# MCU.net
KiCad netlist of a schematic drawn in Altium Designer
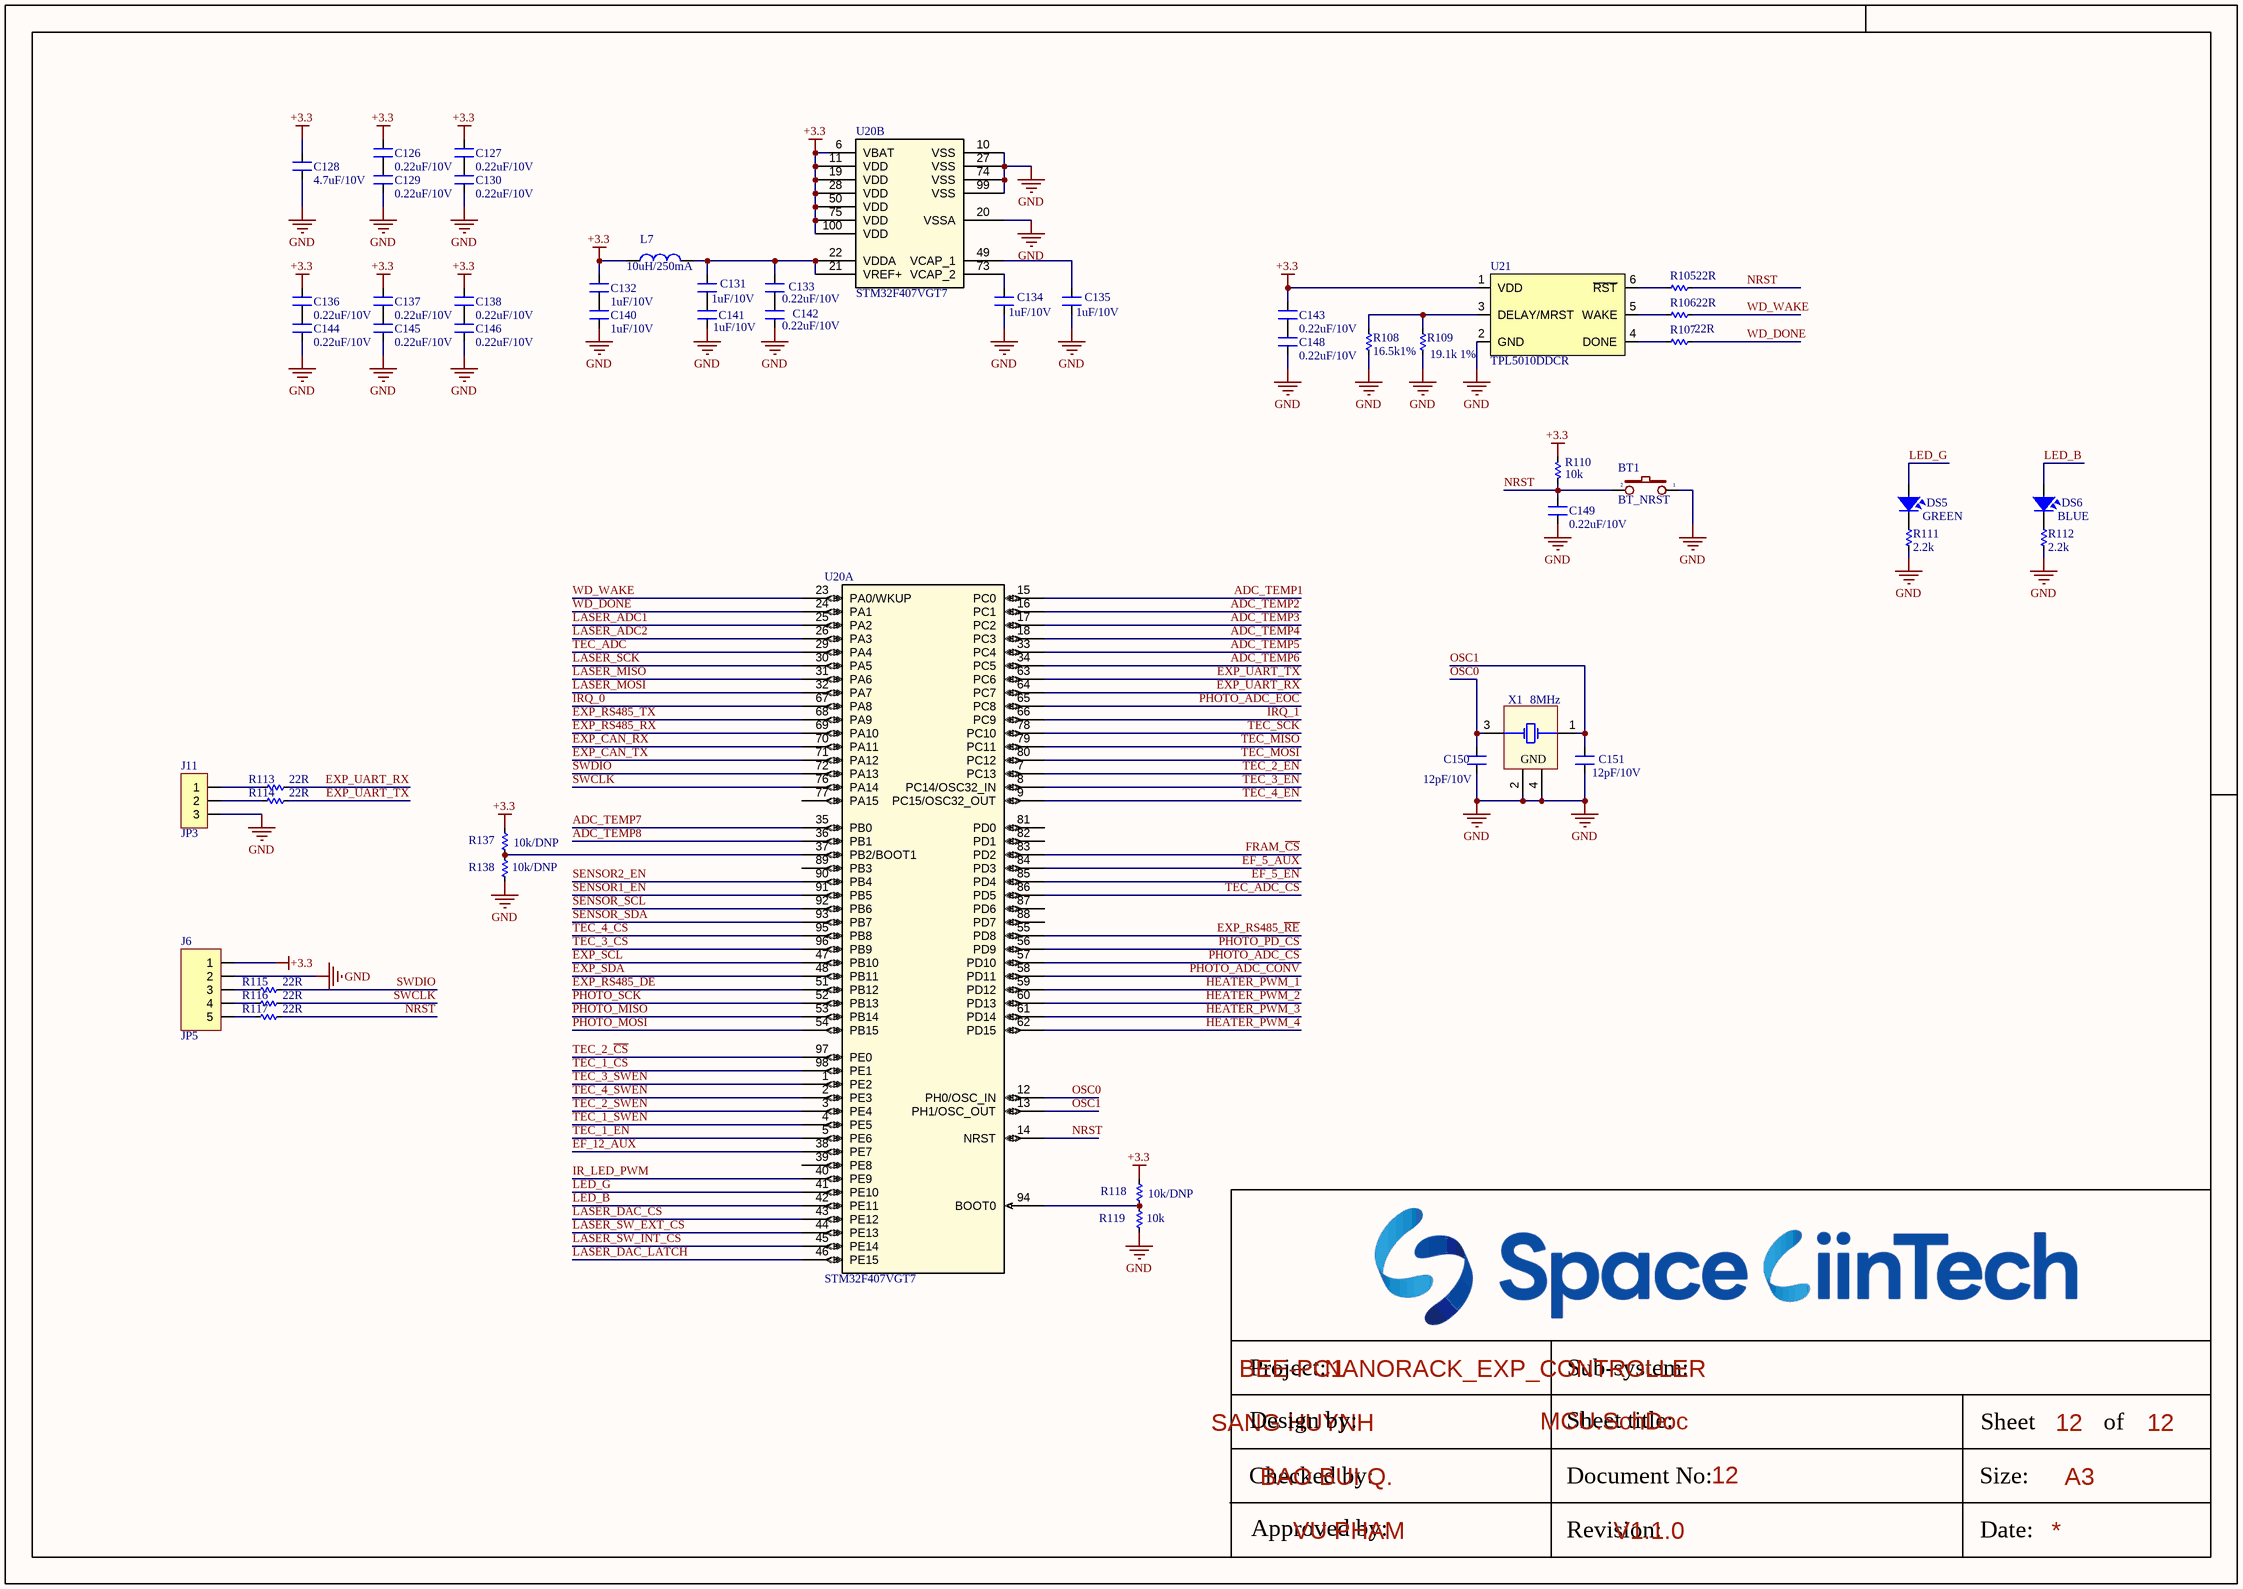
[diagram p0: MCU.SchDoc]

(export (version "E")
  (design (tool "Eeschema 10.0.6"))
  (components
    (comp (ref "BT1")
      (value "BT_NRST")
      (footprint "SW1-SMD")
      (description "Switch button 2 pin")
      (libsource (lib "Sang_library") (part "SW2"))
    )
    (comp (ref "C126")
      (value "0.22uF/10V")
      (footprint "CAP_C_1608X80")
      (libsource (lib "Sang_library") (part "Capacitors"))
    )
    (comp (ref "C127")
      (value "0.22uF/10V")
      (footprint "CAP_C_1608X80")
      (libsource (lib "Sang_library") (part "Capacitors"))
    )
    (comp (ref "C128")
      (value "4.7uF/10V")
      (footprint "CAP_C_1608X80")
      (libsource (lib "Sang_library") (part "Capacitors"))
    )
    (comp (ref "C129")
      (value "0.22uF/10V")
      (footprint "CAP_C_1608X80")
      (libsource (lib "Sang_library") (part "Capacitors"))
    )
    (comp (ref "C130")
      (value "0.22uF/10V")
      (footprint "CAP_C_1608X80")
      (libsource (lib "Sang_library") (part "Capacitors"))
    )
    (comp (ref "C131")
      (value "1uF/10V")
      (footprint "CAP_C_1608X80")
      (libsource (lib "Sang_library") (part "Capacitors"))
    )
    (comp (ref "C132")
      (value "1uF/10V")
      (footprint "CAP_C_1608X80")
      (libsource (lib "Sang_library") (part "Capacitors"))
    )
    (comp (ref "C133")
      (value "0.22uF/10V")
      (footprint "CAP_C_1608X80")
      (libsource (lib "Sang_library") (part "Capacitors"))
    )
    (comp (ref "C134")
      (value "1uF/10V")
      (footprint "CAP_C_1608X80")
      (libsource (lib "Sang_library") (part "Capacitors"))
    )
    (comp (ref "C135")
      (value "1uF/10V")
      (footprint "CAP_C_1608X80")
      (libsource (lib "Sang_library") (part "Capacitors"))
    )
    (comp (ref "C136")
      (value "0.22uF/10V")
      (footprint "CAP_C_1608X80")
      (libsource (lib "Sang_library") (part "Capacitors"))
    )
    (comp (ref "C137")
      (value "0.22uF/10V")
      (footprint "CAP_C_1608X80")
      (libsource (lib "Sang_library") (part "Capacitors"))
    )
    (comp (ref "C138")
      (value "0.22uF/10V")
      (footprint "CAP_C_1608X80")
      (libsource (lib "Sang_library") (part "Capacitors"))
    )
    (comp (ref "C140")
      (value "1uF/10V")
      (footprint "CAP_C_1608X80")
      (libsource (lib "Sang_library") (part "Capacitors"))
    )
    (comp (ref "C141")
      (value "1uF/10V")
      (footprint "CAP_C_1608X80")
      (libsource (lib "Sang_library") (part "Capacitors"))
    )
    (comp (ref "C142")
      (value "0.22uF/10V")
      (footprint "CAP_C_1608X80")
      (libsource (lib "Sang_library") (part "Capacitors"))
    )
    (comp (ref "C143")
      (value "0.22uF/10V")
      (footprint "CAP_C_1608X80")
      (libsource (lib "Sang_library") (part "Capacitors"))
    )
    (comp (ref "C144")
      (value "0.22uF/10V")
      (footprint "CAP_C_1608X80")
      (libsource (lib "Sang_library") (part "Capacitors"))
    )
    (comp (ref "C145")
      (value "0.22uF/10V")
      (footprint "CAP_C_1608X80")
      (libsource (lib "Sang_library") (part "Capacitors"))
    )
    (comp (ref "C146")
      (value "0.22uF/10V")
      (footprint "CAP_C_1608X80")
      (libsource (lib "Sang_library") (part "Capacitors"))
    )
    (comp (ref "C148")
      (value "0.22uF/10V")
      (footprint "CAP_C_1608X80")
      (libsource (lib "Sang_library") (part "Capacitors"))
    )
    (comp (ref "C149")
      (value "0.22uF/10V")
      (footprint "CAP_C_1608X80")
      (libsource (lib "Sang_library") (part "Capacitors"))
    )
    (comp (ref "C150")
      (value "12pF/10V")
      (footprint "CAP_C_1608X80")
      (libsource (lib "Sang_library") (part "Capacitors"))
    )
    (comp (ref "C151")
      (value "12pF/10V")
      (footprint "CAP_C_1608X80")
      (libsource (lib "Sang_library") (part "Capacitors"))
    )
    (comp (ref "DS5")
      (value "GREEN")
      (footprint "LED-0603-BLUE-EXP-V110")
      (libsource (lib "Sang_library") (part "LED SMD"))
    )
    (comp (ref "DS6")
      (value "BLUE")
      (footprint "LED-0603-BLUE-EXP-V110")
      (libsource (lib "Sang_library") (part "LED SMD"))
    )
    (comp (ref "J6")
      (value "JP5")
      (footprint "JP5-D1C")
      (description "WR-PHD 2.54 mm Angled Socket Header")
      (fields
        (field (name "MANUFACTURER") "Würth Elektronik eiSos GmbH")
        (field (name "PARTNO") "613005143121")
        (field (name "CREATED BY") "Karrer Zheng")
      )
      (libsource (lib "Sang_library") (part "JP5"))
    )
    (comp (ref "J11")
      (value "JP3")
      (footprint "JP3-D1C")
      (description "WR-PHD 2.54 mm Angled Socket Header")
      (fields
        (field (name "MANUFACTURER") "Würth Elektronik eiSos GmbH")
        (field (name "PARTNO") "613003143121")
        (field (name "CREATED BY") "Karrer Zheng")
      )
      (libsource (lib "Sang_library") (part "JP3"))
    )
    (comp (ref "L7")
      (value "10uH/250mA")
      (footprint "L-SMD-0603-EXP-V101")
      (fields
        (field (name "PARTNO") "78477010")
        (field (name "MANUFACTURER") "Wurth Elektronik")
        (field (name "CREATED BY") "Baojun Chen")
      )
      (libsource (lib "Sang_library") (part "L-SMD-1"))
    )
    (comp (ref "R105")
      (value "22R")
      (footprint "RES_C_1608X60")
      (description "SMD")
      (fields
        (field (name "MANUFACTURER") "Generic Components")
        (field (name "PUBLISHER") "Altium Hobart Technology Centre")
      )
      (libsource (lib "Sang_library") (part "Res SMD"))
    )
    (comp (ref "R106")
      (value "22R")
      (footprint "RES_C_1608X60")
      (description "SMD")
      (fields
        (field (name "MANUFACTURER") "Generic Components")
        (field (name "PUBLISHER") "Altium Hobart Technology Centre")
      )
      (libsource (lib "Sang_library") (part "Res SMD"))
    )
    (comp (ref "R107")
      (value "22R")
      (footprint "RES_C_1608X60")
      (description "SMD")
      (fields
        (field (name "MANUFACTURER") "Generic Components")
        (field (name "PUBLISHER") "Altium Hobart Technology Centre")
      )
      (libsource (lib "Sang_library") (part "Res SMD"))
    )
    (comp (ref "R108")
      (value "16.5k1%")
      (footprint "RES_C_1608X60")
      (description "SMD")
      (fields
        (field (name "MANUFACTURER") "Generic Components")
        (field (name "PUBLISHER") "Altium Hobart Technology Centre")
      )
      (libsource (lib "Sang_library") (part "Res SMD"))
    )
    (comp (ref "R109")
      (value "19.1k 1%")
      (footprint "RES_C_1608X60")
      (description "SMD")
      (fields
        (field (name "MANUFACTURER") "Generic Components")
        (field (name "PUBLISHER") "Altium Hobart Technology Centre")
      )
      (libsource (lib "Sang_library") (part "Res SMD"))
    )
    (comp (ref "R110")
      (value "10k")
      (footprint "RES_C_1608X60")
      (description "SMD")
      (fields
        (field (name "MANUFACTURER") "Generic Components")
        (field (name "PUBLISHER") "Altium Hobart Technology Centre")
      )
      (libsource (lib "Sang_library") (part "Res SMD"))
    )
    (comp (ref "R111")
      (value "2.2k")
      (footprint "RES_C_1608X60")
      (description "SMD")
      (fields
        (field (name "MANUFACTURER") "Generic Components")
        (field (name "PUBLISHER") "Altium Hobart Technology Centre")
      )
      (libsource (lib "Sang_library") (part "Res SMD"))
    )
    (comp (ref "R112")
      (value "2.2k")
      (footprint "RES_C_1608X60")
      (description "SMD")
      (fields
        (field (name "MANUFACTURER") "Generic Components")
        (field (name "PUBLISHER") "Altium Hobart Technology Centre")
      )
      (libsource (lib "Sang_library") (part "Res SMD"))
    )
    (comp (ref "R113")
      (value "22R")
      (footprint "RES_C_1608X60")
      (description "SMD")
      (fields
        (field (name "MANUFACTURER") "Generic Components")
        (field (name "PUBLISHER") "Altium Hobart Technology Centre")
      )
      (libsource (lib "Sang_library") (part "Res SMD"))
    )
    (comp (ref "R114")
      (value "22R")
      (footprint "RES_C_1608X60")
      (description "SMD")
      (fields
        (field (name "MANUFACTURER") "Generic Components")
        (field (name "PUBLISHER") "Altium Hobart Technology Centre")
      )
      (libsource (lib "Sang_library") (part "Res SMD"))
    )
    (comp (ref "R115")
      (value "22R")
      (footprint "RES_C_1608X60")
      (description "SMD")
      (fields
        (field (name "MANUFACTURER") "Generic Components")
        (field (name "PUBLISHER") "Altium Hobart Technology Centre")
      )
      (libsource (lib "Sang_library") (part "Res SMD"))
    )
    (comp (ref "R116")
      (value "22R")
      (footprint "RES_C_1608X60")
      (description "SMD")
      (fields
        (field (name "MANUFACTURER") "Generic Components")
        (field (name "PUBLISHER") "Altium Hobart Technology Centre")
      )
      (libsource (lib "Sang_library") (part "Res SMD"))
    )
    (comp (ref "R117")
      (value "22R")
      (footprint "RES_C_1608X60")
      (description "SMD")
      (fields
        (field (name "MANUFACTURER") "Generic Components")
        (field (name "PUBLISHER") "Altium Hobart Technology Centre")
      )
      (libsource (lib "Sang_library") (part "Res SMD"))
    )
    (comp (ref "R118")
      (value "10k/DNP")
      (footprint "RES_C_1608X60")
      (description "SMD")
      (fields
        (field (name "MANUFACTURER") "Generic Components")
        (field (name "PUBLISHER") "Altium Hobart Technology Centre")
      )
      (libsource (lib "Sang_library") (part "Res SMD"))
    )
    (comp (ref "R119")
      (value "10k")
      (footprint "RES_C_1608X60")
      (description "SMD")
      (fields
        (field (name "MANUFACTURER") "Generic Components")
        (field (name "PUBLISHER") "Altium Hobart Technology Centre")
      )
      (libsource (lib "Sang_library") (part "Res SMD"))
    )
    (comp (ref "R137")
      (value "10k/DNP")
      (footprint "RES_C_1608X60")
      (description "SMD")
      (fields
        (field (name "MANUFACTURER") "Generic Components")
        (field (name "PUBLISHER") "Altium Hobart Technology Centre")
      )
      (libsource (lib "Sang_library") (part "Res SMD"))
    )
    (comp (ref "R138")
      (value "10k/DNP")
      (footprint "RES_C_1608X60")
      (description "SMD")
      (fields
        (field (name "MANUFACTURER") "Generic Components")
        (field (name "PUBLISHER") "Altium Hobart Technology Centre")
      )
      (libsource (lib "Sang_library") (part "Res SMD"))
    )
    (comp (ref "U20")
      (value "STM32F407VGT7")
      (footprint "LQFP-100-EXP-V110")
      (libsource (lib "Sang_library") (part "STM32F407VGT7"))
    )
    (comp (ref "U21")
      (value "TPL5010DDCR")
      (footprint "TPL5010DDCR_EXP_V110")
      (description "IC OSC PROG TIMER TSOT23-6")
      (libsource (lib "Sang_library") (part "TPL5010DDCR"))
    )
    (comp (ref "X1")
      (value "8MHz")
      (footprint "XT4-16.000MHz-4_V")
      (description "Crystal, 8 MHz, -30 to 85 degC, 3.2 x 2.5 x 0.9 mm SMD")
      (libsource (lib "Library") (part "XT4"))
    )
  )
  (nets
    (net (code "1") (name "+3.3") (class "Default")
      (node (ref "C126") (pin "2") (pinfunction "2_2") (pintype "passive"))
      (node (ref "C127") (pin "2") (pinfunction "2_2") (pintype "passive"))
      (node (ref "C128") (pin "2") (pinfunction "2_2") (pintype "passive"))
      (node (ref "C132") (pin "2") (pinfunction "2_2") (pintype "passive"))
      (node (ref "C136") (pin "2") (pinfunction "2_2") (pintype "passive"))
      (node (ref "C137") (pin "2") (pinfunction "2_2") (pintype "passive"))
      (node (ref "C138") (pin "2") (pinfunction "2_2") (pintype "passive"))
      (node (ref "C143") (pin "2") (pinfunction "2_2") (pintype "passive"))
      (node (ref "J6") (pin "1") (pinfunction "1_1") (pintype "passive"))
      (node (ref "L7") (pin "1") (pinfunction "1_1") (pintype "passive"))
      (node (ref "R110") (pin "1") (pinfunction "1_1") (pintype "passive"))
      (node (ref "R118") (pin "1") (pinfunction "1_1") (pintype "passive"))
      (node (ref "R137") (pin "1") (pinfunction "1_1") (pintype "passive"))
      (node (ref "U20") (pin "100") (pinfunction "VDD_100") (pintype "power_in"))
      (node (ref "U20") (pin "11") (pinfunction "VDD_11") (pintype "power_in"))
      (node (ref "U20") (pin "19") (pinfunction "VDD_19") (pintype "power_in"))
      (node (ref "U20") (pin "28") (pinfunction "VDD_28") (pintype "power_in"))
      (node (ref "U20") (pin "50") (pinfunction "VDD_50") (pintype "power_in"))
      (node (ref "U20") (pin "6") (pinfunction "VBAT_6") (pintype "power_in"))
      (node (ref "U20") (pin "75") (pinfunction "VDD_75") (pintype "power_in"))
      (node (ref "U21") (pin "1") (pinfunction "VDD_1") (pintype "passive"))
    )
    (net (code "2") (name "/ADC_TEMP1") (class "Default")
      (node (ref "U20") (pin "15") (pinfunction "PC0_15") (pintype "bidirectional"))
    )
    (net (code "3") (name "/ADC_TEMP2") (class "Default")
      (node (ref "U20") (pin "16") (pinfunction "PC1_16") (pintype "bidirectional"))
    )
    (net (code "4") (name "/ADC_TEMP3") (class "Default")
      (node (ref "U20") (pin "17") (pinfunction "PC2_17") (pintype "bidirectional"))
    )
    (net (code "5") (name "/ADC_TEMP4") (class "Default")
      (node (ref "U20") (pin "18") (pinfunction "PC3_18") (pintype "bidirectional"))
    )
    (net (code "6") (name "/ADC_TEMP5") (class "Default")
      (node (ref "U20") (pin "33") (pinfunction "PC4_33") (pintype "bidirectional"))
    )
    (net (code "7") (name "/ADC_TEMP6") (class "Default")
      (node (ref "U20") (pin "34") (pinfunction "PC5_34") (pintype "bidirectional"))
    )
    (net (code "8") (name "/ADC_TEMP7") (class "Default")
      (node (ref "U20") (pin "35") (pinfunction "PB0_35") (pintype "bidirectional"))
    )
    (net (code "9") (name "/ADC_TEMP8") (class "Default")
      (node (ref "U20") (pin "36") (pinfunction "PB1_36") (pintype "bidirectional"))
    )
    (net (code "10") (name "/EF_5_AUX") (class "Default")
      (node (ref "U20") (pin "84") (pinfunction "PD3_84") (pintype "bidirectional"))
    )
    (net (code "11") (name "/EF_5_EN") (class "Default")
      (node (ref "U20") (pin "85") (pinfunction "PD4_85") (pintype "bidirectional"))
    )
    (net (code "12") (name "/EF_12_AUX") (class "Default")
      (node (ref "U20") (pin "38") (pinfunction "PE7_38") (pintype "bidirectional"))
    )
    (net (code "13") (name "/EXP_CAN_RX") (class "Default")
      (node (ref "U20") (pin "70") (pinfunction "PA11_70") (pintype "bidirectional"))
    )
    (net (code "14") (name "/EXP_CAN_TX") (class "Default")
      (node (ref "U20") (pin "71") (pinfunction "PA12_71") (pintype "bidirectional"))
    )
    (net (code "15") (name "/EXP_RS485_DE") (class "Default")
      (node (ref "U20") (pin "51") (pinfunction "PB12_51") (pintype "bidirectional"))
    )
    (net (code "16") (name "/EXP_RS485_RX") (class "Default")
      (node (ref "U20") (pin "69") (pinfunction "PA10_69") (pintype "bidirectional"))
    )
    (net (code "17") (name "/EXP_RS485_TX") (class "Default")
      (node (ref "U20") (pin "68") (pinfunction "PA9_68") (pintype "bidirectional"))
    )
    (net (code "18") (name "/EXP_RS485_~{RE}") (class "Default")
      (node (ref "U20") (pin "55") (pinfunction "PD8_55") (pintype "bidirectional"))
    )
    (net (code "19") (name "/EXP_SCL") (class "Default")
      (node (ref "U20") (pin "47") (pinfunction "PB10_47") (pintype "bidirectional"))
    )
    (net (code "20") (name "/EXP_SDA") (class "Default")
      (node (ref "U20") (pin "48") (pinfunction "PB11_48") (pintype "bidirectional"))
    )
    (net (code "21") (name "/EXP_UART_RX") (class "Default")
      (node (ref "R113") (pin "1") (pinfunction "1_1") (pintype "passive"))
      (node (ref "U20") (pin "64") (pinfunction "PC7_64") (pintype "bidirectional"))
    )
    (net (code "22") (name "/EXP_UART_TX") (class "Default")
      (node (ref "R114") (pin "1") (pinfunction "1_1") (pintype "passive"))
      (node (ref "U20") (pin "63") (pinfunction "PC6_63") (pintype "bidirectional"))
    )
    (net (code "23") (name "/FRAM_~{CS}") (class "Default")
      (node (ref "U20") (pin "83") (pinfunction "PD2_83") (pintype "bidirectional"))
    )
    (net (code "24") (name "/HEATER_PWM_1") (class "Default")
      (node (ref "U20") (pin "59") (pinfunction "PD12_59") (pintype "bidirectional"))
    )
    (net (code "25") (name "/HEATER_PWM_2") (class "Default")
      (node (ref "U20") (pin "60") (pinfunction "PD13_60") (pintype "bidirectional"))
    )
    (net (code "26") (name "/HEATER_PWM_3") (class "Default")
      (node (ref "U20") (pin "61") (pinfunction "PD14_61") (pintype "bidirectional"))
    )
    (net (code "27") (name "/HEATER_PWM_4") (class "Default")
      (node (ref "U20") (pin "62") (pinfunction "PD15_62") (pintype "bidirectional"))
    )
    (net (code "28") (name "/IRQ_0") (class "Default")
      (node (ref "U20") (pin "67") (pinfunction "PA8_67") (pintype "bidirectional"))
    )
    (net (code "29") (name "/IRQ_1") (class "Default")
      (node (ref "U20") (pin "66") (pinfunction "PC9_66") (pintype "bidirectional"))
    )
    (net (code "30") (name "/IR_LED_PWM") (class "Default")
      (node (ref "U20") (pin "40") (pinfunction "PE9_40") (pintype "bidirectional"))
    )
    (net (code "31") (name "/LASER_ADC1") (class "Default")
      (node (ref "U20") (pin "25") (pinfunction "PA2_25") (pintype "bidirectional"))
    )
    (net (code "32") (name "/LASER_ADC2") (class "Default")
      (node (ref "U20") (pin "26") (pinfunction "PA3_26") (pintype "bidirectional"))
    )
    (net (code "33") (name "/LASER_DAC_CS") (class "Default")
      (node (ref "U20") (pin "43") (pinfunction "PE12_43") (pintype "bidirectional"))
    )
    (net (code "34") (name "/LASER_DAC_LATCH") (class "Default")
      (node (ref "U20") (pin "46") (pinfunction "PE15_46") (pintype "bidirectional"))
    )
    (net (code "35") (name "/LASER_MISO") (class "Default")
      (node (ref "U20") (pin "31") (pinfunction "PA6_31") (pintype "bidirectional"))
    )
    (net (code "36") (name "/LASER_MOSI") (class "Default")
      (node (ref "U20") (pin "32") (pinfunction "PA7_32") (pintype "bidirectional"))
    )
    (net (code "37") (name "/LASER_SCK") (class "Default")
      (node (ref "U20") (pin "30") (pinfunction "PA5_30") (pintype "bidirectional"))
    )
    (net (code "38") (name "/LASER_SW_EXT_CS") (class "Default")
      (node (ref "U20") (pin "44") (pinfunction "PE13_44") (pintype "bidirectional"))
    )
    (net (code "39") (name "/LASER_SW_INT_CS") (class "Default")
      (node (ref "U20") (pin "45") (pinfunction "PE14_45") (pintype "bidirectional"))
    )
    (net (code "40") (name "/LED_B") (class "Default")
      (node (ref "DS6") (pin "1") (pinfunction "1_1") (pintype "passive"))
      (node (ref "U20") (pin "42") (pinfunction "PE11_42") (pintype "bidirectional"))
    )
    (net (code "41") (name "/LED_G") (class "Default")
      (node (ref "DS5") (pin "1") (pinfunction "1_1") (pintype "passive"))
      (node (ref "U20") (pin "41") (pinfunction "PE10_41") (pintype "bidirectional"))
    )
    (net (code "42") (name "/NRST") (class "Default")
      (node (ref "BT1") (pin "2") (pinfunction "2_2") (pintype "passive"))
      (node (ref "C149") (pin "2") (pinfunction "2_2") (pintype "passive"))
      (node (ref "R105") (pin "2") (pinfunction "2_2") (pintype "passive"))
      (node (ref "R110") (pin "2") (pinfunction "2_2") (pintype "passive"))
      (node (ref "R117") (pin "1") (pinfunction "1_1") (pintype "passive"))
      (node (ref "U20") (pin "14") (pinfunction "NRST_14") (pintype "bidirectional"))
    )
    (net (code "43") (name "/OSC0") (class "Default")
      (node (ref "C150") (pin "1") (pinfunction "1_1") (pintype "passive"))
      (node (ref "U20") (pin "12") (pinfunction "PH0/OSC_IN_12") (pintype "bidirectional"))
      (node (ref "X1") (pin "3") (pinfunction "XTAL_3") (pintype "passive"))
    )
    (net (code "44") (name "/OSC1") (class "Default")
      (node (ref "C151") (pin "2") (pinfunction "2_2") (pintype "passive"))
      (node (ref "U20") (pin "13") (pinfunction "PH1/OSC_OUT_13") (pintype "bidirectional"))
      (node (ref "X1") (pin "1") (pinfunction "XTAL_1") (pintype "passive"))
    )
    (net (code "45") (name "/PHOTO_ADC_CONV") (class "Default")
      (node (ref "U20") (pin "58") (pinfunction "PD11_58") (pintype "bidirectional"))
    )
    (net (code "46") (name "/PHOTO_ADC_CS") (class "Default")
      (node (ref "U20") (pin "57") (pinfunction "PD10_57") (pintype "bidirectional"))
    )
    (net (code "47") (name "/PHOTO_ADC_EOC") (class "Default")
      (node (ref "U20") (pin "65") (pinfunction "PC8_65") (pintype "bidirectional"))
    )
    (net (code "48") (name "/PHOTO_MISO") (class "Default")
      (node (ref "U20") (pin "53") (pinfunction "PB14_53") (pintype "bidirectional"))
    )
    (net (code "49") (name "/PHOTO_MOSI") (class "Default")
      (node (ref "U20") (pin "54") (pinfunction "PB15_54") (pintype "bidirectional"))
    )
    (net (code "50") (name "/PHOTO_PD_CS") (class "Default")
      (node (ref "U20") (pin "56") (pinfunction "PD9_56") (pintype "bidirectional"))
    )
    (net (code "51") (name "/PHOTO_SCK") (class "Default")
      (node (ref "U20") (pin "52") (pinfunction "PB13_52") (pintype "bidirectional"))
    )
    (net (code "52") (name "/SENSOR1_EN") (class "Default")
      (node (ref "U20") (pin "91") (pinfunction "PB5_91") (pintype "bidirectional"))
    )
    (net (code "53") (name "/SENSOR2_EN") (class "Default")
      (node (ref "U20") (pin "90") (pinfunction "PB4_90") (pintype "bidirectional"))
    )
    (net (code "54") (name "/SENSOR_SCL") (class "Default")
      (node (ref "U20") (pin "92") (pinfunction "PB6_92") (pintype "bidirectional"))
    )
    (net (code "55") (name "/SENSOR_SDA") (class "Default")
      (node (ref "U20") (pin "93") (pinfunction "PB7_93") (pintype "bidirectional"))
    )
    (net (code "56") (name "/SWCLK") (class "Default")
      (node (ref "R116") (pin "1") (pinfunction "1_1") (pintype "passive"))
      (node (ref "U20") (pin "76") (pinfunction "PA14_76") (pintype "bidirectional"))
    )
    (net (code "57") (name "/SWDIO") (class "Default")
      (node (ref "R115") (pin "1") (pinfunction "1_1") (pintype "passive"))
      (node (ref "U20") (pin "72") (pinfunction "PA13_72") (pintype "bidirectional"))
    )
    (net (code "58") (name "/TEC_1_EN") (class "Default")
      (node (ref "U20") (pin "5") (pinfunction "PE6_5") (pintype "bidirectional"))
    )
    (net (code "59") (name "/TEC_1_SWEN") (class "Default")
      (node (ref "U20") (pin "4") (pinfunction "PE5_4") (pintype "bidirectional"))
    )
    (net (code "60") (name "/TEC_1_~{CS}") (class "Default")
      (node (ref "U20") (pin "98") (pinfunction "PE1_98") (pintype "bidirectional"))
    )
    (net (code "61") (name "/TEC_2_EN") (class "Default")
      (node (ref "U20") (pin "7") (pinfunction "PC13_7") (pintype "bidirectional"))
    )
    (net (code "62") (name "/TEC_2_SWEN") (class "Default")
      (node (ref "U20") (pin "3") (pinfunction "PE4_3") (pintype "bidirectional"))
    )
    (net (code "63") (name "/TEC_2_~{CS}") (class "Default")
      (node (ref "U20") (pin "97") (pinfunction "PE0_97") (pintype "bidirectional"))
    )
    (net (code "64") (name "/TEC_3_EN") (class "Default")
      (node (ref "U20") (pin "8") (pinfunction "PC14/OSC32_IN_8") (pintype "bidirectional"))
    )
    (net (code "65") (name "/TEC_3_SWEN") (class "Default")
      (node (ref "U20") (pin "1") (pinfunction "PE2_1") (pintype "bidirectional"))
    )
    (net (code "66") (name "/TEC_3_~{CS}") (class "Default")
      (node (ref "U20") (pin "96") (pinfunction "PB9_96") (pintype "bidirectional"))
    )
    (net (code "67") (name "/TEC_4_EN") (class "Default")
      (node (ref "U20") (pin "9") (pinfunction "PC15/OSC32_OUT_9") (pintype "bidirectional"))
    )
    (net (code "68") (name "/TEC_4_SWEN") (class "Default")
      (node (ref "U20") (pin "2") (pinfunction "PE3_2") (pintype "bidirectional"))
    )
    (net (code "69") (name "/TEC_4_~{CS}") (class "Default")
      (node (ref "U20") (pin "95") (pinfunction "PB8_95") (pintype "bidirectional"))
    )
    (net (code "70") (name "/TEC_ADC") (class "Default")
      (node (ref "U20") (pin "29") (pinfunction "PA4_29") (pintype "bidirectional"))
    )
    (net (code "71") (name "/TEC_ADC_~{CS}") (class "Default")
      (node (ref "U20") (pin "86") (pinfunction "PD5_86") (pintype "bidirectional"))
    )
    (net (code "72") (name "/TEC_MISO") (class "Default")
      (node (ref "U20") (pin "79") (pinfunction "PC11_79") (pintype "bidirectional"))
    )
    (net (code "73") (name "/TEC_MOSI") (class "Default")
      (node (ref "U20") (pin "80") (pinfunction "PC12_80") (pintype "bidirectional"))
    )
    (net (code "74") (name "/TEC_SCK") (class "Default")
      (node (ref "U20") (pin "78") (pinfunction "PC10_78") (pintype "bidirectional"))
    )
    (net (code "75") (name "/WD_DONE") (class "Default")
      (node (ref "R107") (pin "2") (pinfunction "2_2") (pintype "passive"))
      (node (ref "U20") (pin "24") (pinfunction "PA1_24") (pintype "bidirectional"))
    )
    (net (code "76") (name "/WD_WAKE") (class "Default")
      (node (ref "R106") (pin "2") (pinfunction "2_2") (pintype "passive"))
      (node (ref "U20") (pin "23") (pinfunction "PA0/WKUP_23") (pintype "bidirectional"))
    )
    (net (code "77") (name "GND") (class "Default")
      (node (ref "BT1") (pin "1") (pinfunction "1_1") (pintype "passive"))
      (node (ref "C128") (pin "1") (pinfunction "1_1") (pintype "passive"))
      (node (ref "C129") (pin "1") (pinfunction "1_1") (pintype "passive"))
      (node (ref "C130") (pin "1") (pinfunction "1_1") (pintype "passive"))
      (node (ref "C134") (pin "1") (pinfunction "1_1") (pintype "passive"))
      (node (ref "C135") (pin "1") (pinfunction "1_1") (pintype "passive"))
      (node (ref "C140") (pin "1") (pinfunction "1_1") (pintype "passive"))
      (node (ref "C141") (pin "1") (pinfunction "1_1") (pintype "passive"))
      (node (ref "C142") (pin "1") (pinfunction "1_1") (pintype "passive"))
      (node (ref "C144") (pin "1") (pinfunction "1_1") (pintype "passive"))
      (node (ref "C145") (pin "1") (pinfunction "1_1") (pintype "passive"))
      (node (ref "C146") (pin "1") (pinfunction "1_1") (pintype "passive"))
      (node (ref "C148") (pin "1") (pinfunction "1_1") (pintype "passive"))
      (node (ref "C149") (pin "1") (pinfunction "1_1") (pintype "passive"))
      (node (ref "C150") (pin "2") (pinfunction "2_2") (pintype "passive"))
      (node (ref "C151") (pin "1") (pinfunction "1_1") (pintype "passive"))
      (node (ref "J11") (pin "3") (pinfunction "3_3") (pintype "passive"))
      (node (ref "J6") (pin "2") (pinfunction "2_2") (pintype "passive"))
      (node (ref "R108") (pin "1") (pinfunction "1_1") (pintype "passive"))
      (node (ref "R109") (pin "1") (pinfunction "1_1") (pintype "passive"))
      (node (ref "R111") (pin "2") (pinfunction "2_2") (pintype "passive"))
      (node (ref "R112") (pin "2") (pinfunction "2_2") (pintype "passive"))
      (node (ref "R119") (pin "2") (pinfunction "2_2") (pintype "passive"))
      (node (ref "R138") (pin "2") (pinfunction "2_2") (pintype "passive"))
      (node (ref "U20") (pin "10") (pinfunction "VSS_10") (pintype "power_in"))
      (node (ref "U20") (pin "20") (pinfunction "VSSA_20") (pintype "power_in"))
      (node (ref "U20") (pin "27") (pinfunction "VSS_27") (pintype "power_in"))
      (node (ref "U20") (pin "74") (pinfunction "VSS_74") (pintype "power_in"))
      (node (ref "U20") (pin "99") (pinfunction "VSS_99") (pintype "power_in"))
      (node (ref "U21") (pin "2") (pinfunction "GND_2") (pintype "passive"))
      (node (ref "X1") (pin "2") (pinfunction "GND_2") (pintype "power_in"))
      (node (ref "X1") (pin "4") (pinfunction "GND_4") (pintype "power_in"))
    )
    (net (code "78") (name "Net-(C126-Pad1)") (class "Default")
      (node (ref "C126") (pin "1") (pinfunction "1_1") (pintype "passive"))
      (node (ref "C129") (pin "2") (pinfunction "2_2") (pintype "passive"))
    )
    (net (code "79") (name "Net-(C127-Pad1)") (class "Default")
      (node (ref "C127") (pin "1") (pinfunction "1_1") (pintype "passive"))
      (node (ref "C130") (pin "2") (pinfunction "2_2") (pintype "passive"))
    )
    (net (code "80") (name "Net-(C131-Pad1)") (class "Default")
      (node (ref "C131") (pin "1") (pinfunction "1_1") (pintype "passive"))
      (node (ref "C141") (pin "2") (pinfunction "2_2") (pintype "passive"))
    )
    (net (code "81") (name "Net-(C132-Pad1)") (class "Default")
      (node (ref "C132") (pin "1") (pinfunction "1_1") (pintype "passive"))
      (node (ref "C140") (pin "2") (pinfunction "2_2") (pintype "passive"))
    )
    (net (code "82") (name "Net-(C133-Pad1)") (class "Default")
      (node (ref "C133") (pin "1") (pinfunction "1_1") (pintype "passive"))
      (node (ref "C142") (pin "2") (pinfunction "2_2") (pintype "passive"))
    )
    (net (code "83") (name "Net-(C136-Pad1)") (class "Default")
      (node (ref "C136") (pin "1") (pinfunction "1_1") (pintype "passive"))
      (node (ref "C144") (pin "2") (pinfunction "2_2") (pintype "passive"))
    )
    (net (code "84") (name "Net-(C137-Pad1)") (class "Default")
      (node (ref "C137") (pin "1") (pinfunction "1_1") (pintype "passive"))
      (node (ref "C145") (pin "2") (pinfunction "2_2") (pintype "passive"))
    )
    (net (code "85") (name "Net-(C138-Pad1)") (class "Default")
      (node (ref "C138") (pin "1") (pinfunction "1_1") (pintype "passive"))
      (node (ref "C146") (pin "2") (pinfunction "2_2") (pintype "passive"))
    )
    (net (code "86") (name "Net-(C143-Pad1)") (class "Default")
      (node (ref "C143") (pin "1") (pinfunction "1_1") (pintype "passive"))
      (node (ref "C148") (pin "2") (pinfunction "2_2") (pintype "passive"))
    )
    (net (code "87") (name "Net-(DS5-Pad2)") (class "Default")
      (node (ref "DS5") (pin "2") (pinfunction "2_2") (pintype "passive"))
      (node (ref "R111") (pin "1") (pinfunction "1_1") (pintype "passive"))
    )
    (net (code "88") (name "Net-(DS6-Pad2)") (class "Default")
      (node (ref "DS6") (pin "2") (pinfunction "2_2") (pintype "passive"))
      (node (ref "R112") (pin "1") (pinfunction "1_1") (pintype "passive"))
    )
    (net (code "89") (name "Net-(J6-Pad3)") (class "Default")
      (node (ref "J6") (pin "3") (pinfunction "3_3") (pintype "passive"))
      (node (ref "R115") (pin "2") (pinfunction "2_2") (pintype "passive"))
    )
    (net (code "90") (name "Net-(J6-Pad4)") (class "Default")
      (node (ref "J6") (pin "4") (pinfunction "4_4") (pintype "passive"))
      (node (ref "R116") (pin "2") (pinfunction "2_2") (pintype "passive"))
    )
    (net (code "91") (name "Net-(J6-Pad5)") (class "Default")
      (node (ref "J6") (pin "5") (pinfunction "5_5") (pintype "passive"))
      (node (ref "R117") (pin "2") (pinfunction "2_2") (pintype "passive"))
    )
    (net (code "92") (name "Net-(J11-Pad1)") (class "Default")
      (node (ref "J11") (pin "1") (pinfunction "1_1") (pintype "passive"))
      (node (ref "R113") (pin "2") (pinfunction "2_2") (pintype "passive"))
    )
    (net (code "93") (name "Net-(J11-Pad2)") (class "Default")
      (node (ref "J11") (pin "2") (pinfunction "2_2") (pintype "passive"))
      (node (ref "R114") (pin "2") (pinfunction "2_2") (pintype "passive"))
    )
    (net (code "94") (name "Net-(U20A-BOOT0)") (class "Default")
      (node (ref "R118") (pin "2") (pinfunction "2_2") (pintype "passive"))
      (node (ref "R119") (pin "1") (pinfunction "1_1") (pintype "passive"))
      (node (ref "U20") (pin "94") (pinfunction "BOOT0_94") (pintype "input"))
    )
    (net (code "95") (name "Net-(U20A-PB2{slash}BOOT1)") (class "Default")
      (node (ref "R137") (pin "2") (pinfunction "2_2") (pintype "passive"))
      (node (ref "R138") (pin "1") (pinfunction "1_1") (pintype "passive"))
      (node (ref "U20") (pin "37") (pinfunction "PB2/BOOT1_37") (pintype "bidirectional"))
    )
    (net (code "96") (name "Net-(U20B-VCAP_1)") (class "Default")
      (node (ref "C135") (pin "2") (pinfunction "2_2") (pintype "passive"))
      (node (ref "U20") (pin "49") (pinfunction "VCAP_1_49") (pintype "power_in"))
    )
    (net (code "97") (name "Net-(U20B-VCAP_2)") (class "Default")
      (node (ref "C134") (pin "2") (pinfunction "2_2") (pintype "passive"))
      (node (ref "U20") (pin "73") (pinfunction "VCAP_2_73") (pintype "power_in"))
    )
    (net (code "98") (name "Net-(U20B-VDDA)") (class "Default")
      (node (ref "C131") (pin "2") (pinfunction "2_2") (pintype "passive"))
      (node (ref "C133") (pin "2") (pinfunction "2_2") (pintype "passive"))
      (node (ref "L7") (pin "2") (pinfunction "2_2") (pintype "passive"))
      (node (ref "U20") (pin "21") (pinfunction "VREF+_21") (pintype "power_in"))
      (node (ref "U20") (pin "22") (pinfunction "VDDA_22") (pintype "power_in"))
    )
    (net (code "99") (name "Net-(U21-DELAY{slash}MRST)") (class "Default")
      (node (ref "R108") (pin "2") (pinfunction "2_2") (pintype "passive"))
      (node (ref "R109") (pin "2") (pinfunction "2_2") (pintype "passive"))
      (node (ref "U21") (pin "3") (pinfunction "DELAY/MRST_3") (pintype "passive"))
    )
    (net (code "100") (name "Net-(U21-DONE)") (class "Default")
      (node (ref "R107") (pin "1") (pinfunction "1_1") (pintype "passive"))
      (node (ref "U21") (pin "4") (pinfunction "DONE_4") (pintype "passive"))
    )
    (net (code "101") (name "Net-(U21-WAKE)") (class "Default")
      (node (ref "R106") (pin "1") (pinfunction "1_1") (pintype "passive"))
      (node (ref "U21") (pin "5") (pinfunction "WAKE_5") (pintype "passive"))
    )
    (net (code "102") (name "Net-(U21-~{RST})") (class "Default")
      (node (ref "R105") (pin "1") (pinfunction "1_1") (pintype "passive"))
      (node (ref "U21") (pin "6") (pinfunction "~{RST}_6") (pintype "passive"))
    )
    (net (code "103") (name "unconnected-(U20A-PA15-Pad77)") (class "Default")
      (node (ref "U20") (pin "77") (pinfunction "PA15_77") (pintype "bidirectional"))
    )
    (net (code "104") (name "unconnected-(U20A-PB3-Pad89)") (class "Default")
      (node (ref "U20") (pin "89") (pinfunction "PB3_89") (pintype "bidirectional"))
    )
    (net (code "105") (name "unconnected-(U20A-PD0-Pad81)") (class "Default")
      (node (ref "U20") (pin "81") (pinfunction "PD0_81") (pintype "bidirectional"))
    )
    (net (code "106") (name "unconnected-(U20A-PD1-Pad82)") (class "Default")
      (node (ref "U20") (pin "82") (pinfunction "PD1_82") (pintype "bidirectional"))
    )
    (net (code "107") (name "unconnected-(U20A-PD6-Pad87)") (class "Default")
      (node (ref "U20") (pin "87") (pinfunction "PD6_87") (pintype "bidirectional"))
    )
    (net (code "108") (name "unconnected-(U20A-PD7-Pad88)") (class "Default")
      (node (ref "U20") (pin "88") (pinfunction "PD7_88") (pintype "bidirectional"))
    )
    (net (code "109") (name "unconnected-(U20A-PE8-Pad39)") (class "Default")
      (node (ref "U20") (pin "39") (pinfunction "PE8_39") (pintype "bidirectional"))
    )
  )
)
